# JTAG20F-JTAG10M.net
KiCad netlist of a schematic drawn in EAGLE
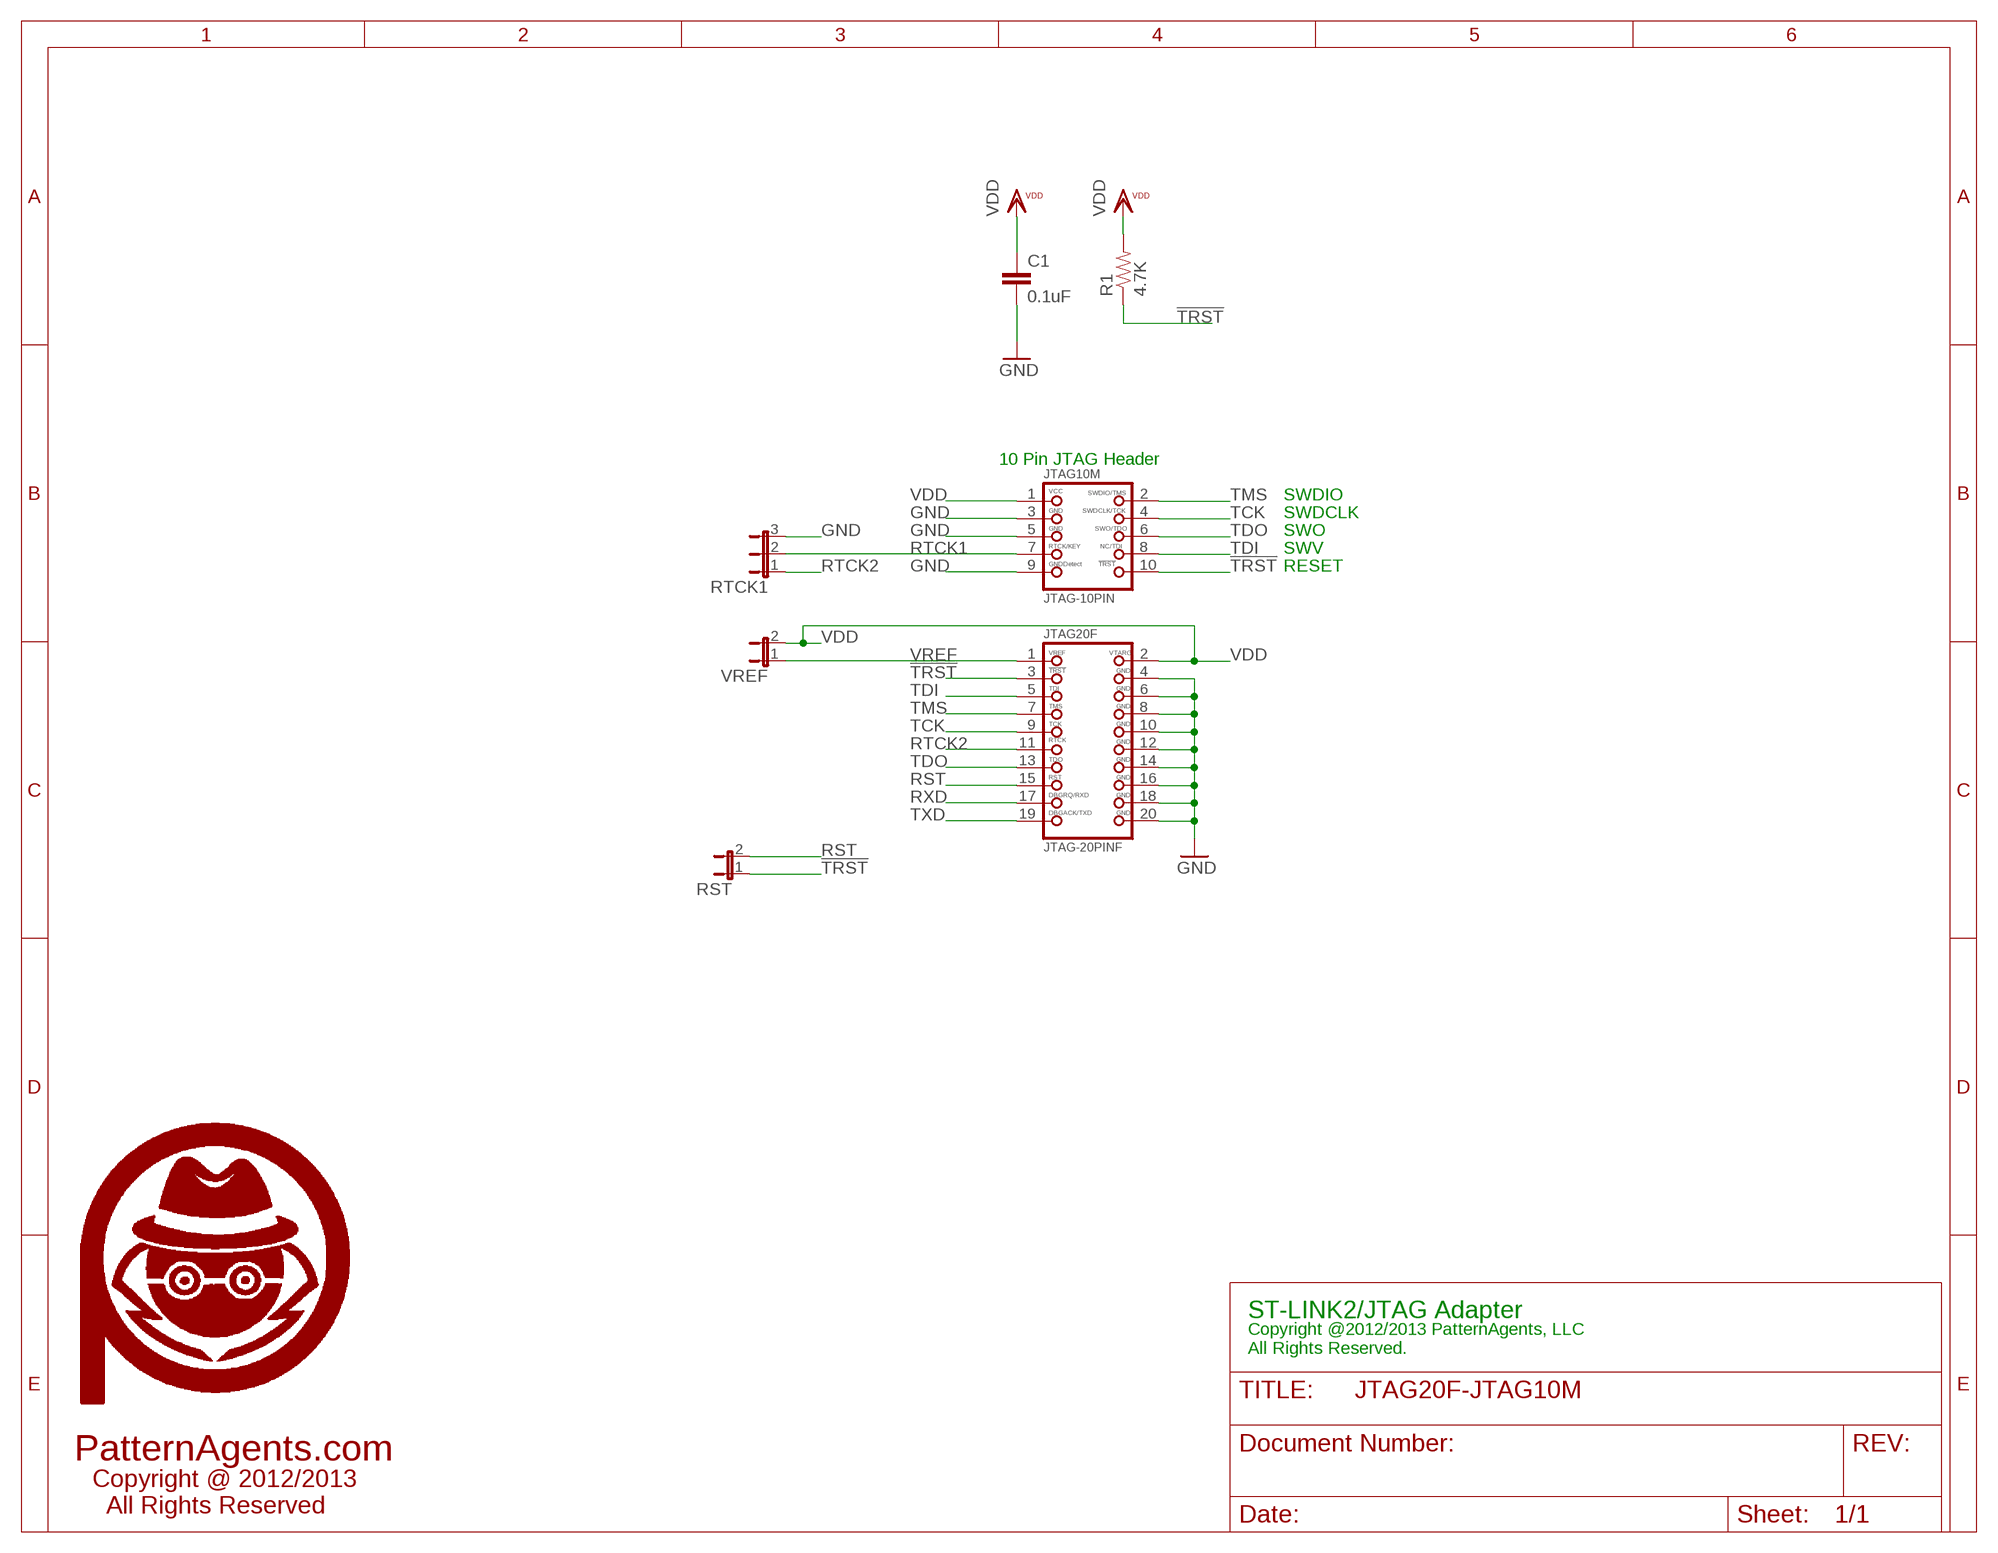
[diagram p0: schematic, sheet 1]

(export (version "E")
  (design (tool "Eeschema 10.0.6"))
  (components
    (comp (ref "C1")
      (value "0.1uF")
      (footprint "eagle-import:0603-CAP")
      (libsource (lib "eagle-import") (part "CAP0603-CAP"))
    )
    (comp (ref "JTAG10M")
      (value "JTAG-10PIN")
      (footprint "eagle-import:2X05_1.27MM_SMT")
      (libsource (lib "eagle-import") (part "JTAG-10PINSMD"))
    )
    (comp (ref "JTAG20F")
      (value "JTAG-20PINF")
      (footprint "eagle-import:2X10F_2.54MM_PTH")
      (libsource (lib "eagle-import") (part "JTAG-20PINF"))
    )
    (comp (ref "R1")
      (value "4.7K")
      (footprint "eagle-import:0603-RES")
      (libsource (lib "eagle-import") (part "RESISTOR_SFE0603-RES"))
    )
    (comp (ref "RST")
      (value "JUMPER2")
      (footprint "eagle-import:JUMPER2")
      (libsource (lib "eagle-import") (part "JUMPER2"))
    )
    (comp (ref "RTCK1")
      (value "JUMPER3")
      (footprint "eagle-import:JUMPER3")
      (libsource (lib "eagle-import") (part "JUMPER3"))
    )
    (comp (ref "U$2")
      (value "PA_LOGO_SYMLARGE")
      (footprint "eagle-import:PA_LOGO_AGENT_LRG_SYM")
      (libsource (lib "eagle-import") (part "PA_LOGO_SYMLARGE"))
    )
    (comp (ref "VREF")
      (value "JUMPER2")
      (footprint "eagle-import:JUMPER2")
      (libsource (lib "eagle-import") (part "JUMPER2"))
    )
  )
  (nets
    (net (code "1") (name "/RST") (class "Default")
      (node (ref "JTAG20F") (pin "15") (pinfunction "15_15") (pintype "passive"))
      (node (ref "RST") (pin "2") (pinfunction "2_2") (pintype "passive"))
    )
    (net (code "2") (name "/RTCK1") (class "Default")
      (node (ref "JTAG10M") (pin "7") (pinfunction "7_7") (pintype "passive"))
      (node (ref "RTCK1") (pin "2") (pinfunction "2_2") (pintype "passive"))
    )
    (net (code "3") (name "/RTCK2") (class "Default")
      (node (ref "JTAG20F") (pin "11") (pinfunction "11_11") (pintype "passive"))
      (node (ref "RTCK1") (pin "1") (pinfunction "1_1") (pintype "passive"))
    )
    (net (code "4") (name "/RXD") (class "Default")
      (node (ref "JTAG20F") (pin "17") (pinfunction "17_17") (pintype "passive"))
    )
    (net (code "5") (name "/TCK") (class "Default")
      (node (ref "JTAG10M") (pin "4") (pinfunction "4_4") (pintype "passive"))
      (node (ref "JTAG20F") (pin "9") (pinfunction "9_9") (pintype "passive"))
    )
    (net (code "6") (name "/TDI") (class "Default")
      (node (ref "JTAG10M") (pin "8") (pinfunction "8_8") (pintype "passive"))
      (node (ref "JTAG20F") (pin "5") (pinfunction "5_5") (pintype "passive"))
    )
    (net (code "7") (name "/TDO") (class "Default")
      (node (ref "JTAG10M") (pin "6") (pinfunction "6_6") (pintype "passive"))
      (node (ref "JTAG20F") (pin "13") (pinfunction "13_13") (pintype "passive"))
    )
    (net (code "8") (name "/TMS") (class "Default")
      (node (ref "JTAG10M") (pin "2") (pinfunction "2_2") (pintype "passive"))
      (node (ref "JTAG20F") (pin "7") (pinfunction "7_7") (pintype "passive"))
    )
    (net (code "9") (name "/TXD") (class "Default")
      (node (ref "JTAG20F") (pin "19") (pinfunction "19_19") (pintype "passive"))
    )
    (net (code "10") (name "/VREF") (class "Default")
      (node (ref "JTAG20F") (pin "1") (pinfunction "1_1") (pintype "passive"))
      (node (ref "VREF") (pin "1") (pinfunction "1_1") (pintype "passive"))
    )
    (net (code "11") (name "/~{TRST}") (class "Default")
      (node (ref "JTAG10M") (pin "10") (pinfunction "10_10") (pintype "passive"))
      (node (ref "JTAG20F") (pin "3") (pinfunction "3_3") (pintype "passive"))
      (node (ref "R1") (pin "1") (pinfunction "1_1") (pintype "passive"))
      (node (ref "RST") (pin "1") (pinfunction "1_1") (pintype "passive"))
    )
    (net (code "12") (name "GND") (class "Default")
      (node (ref "C1") (pin "2") (pinfunction "2_2") (pintype "passive"))
      (node (ref "JTAG10M") (pin "3") (pinfunction "3_3") (pintype "passive"))
      (node (ref "JTAG10M") (pin "5") (pinfunction "5_5") (pintype "passive"))
      (node (ref "JTAG10M") (pin "9") (pinfunction "9_9") (pintype "passive"))
      (node (ref "JTAG20F") (pin "10") (pinfunction "10_10") (pintype "passive"))
      (node (ref "JTAG20F") (pin "12") (pinfunction "12_12") (pintype "passive"))
      (node (ref "JTAG20F") (pin "14") (pinfunction "14_14") (pintype "passive"))
      (node (ref "JTAG20F") (pin "16") (pinfunction "16_16") (pintype "passive"))
      (node (ref "JTAG20F") (pin "18") (pinfunction "18_18") (pintype "passive"))
      (node (ref "JTAG20F") (pin "20") (pinfunction "20_20") (pintype "passive"))
      (node (ref "JTAG20F") (pin "4") (pinfunction "4_4") (pintype "passive"))
      (node (ref "JTAG20F") (pin "6") (pinfunction "6_6") (pintype "passive"))
      (node (ref "JTAG20F") (pin "8") (pinfunction "8_8") (pintype "passive"))
      (node (ref "RTCK1") (pin "3") (pinfunction "3_3") (pintype "passive"))
    )
    (net (code "13") (name "VDD") (class "Default")
      (node (ref "C1") (pin "1") (pinfunction "1_1") (pintype "passive"))
      (node (ref "JTAG10M") (pin "1") (pinfunction "1_1") (pintype "passive"))
      (node (ref "JTAG20F") (pin "2") (pinfunction "2_2") (pintype "passive"))
      (node (ref "R1") (pin "2") (pinfunction "2_2") (pintype "passive"))
      (node (ref "VREF") (pin "2") (pinfunction "2_2") (pintype "passive"))
    )
  )
)
